# LOVE_LED_CARD_2021-05-20.net
KiCad netlist of a schematic drawn in EasyEDA
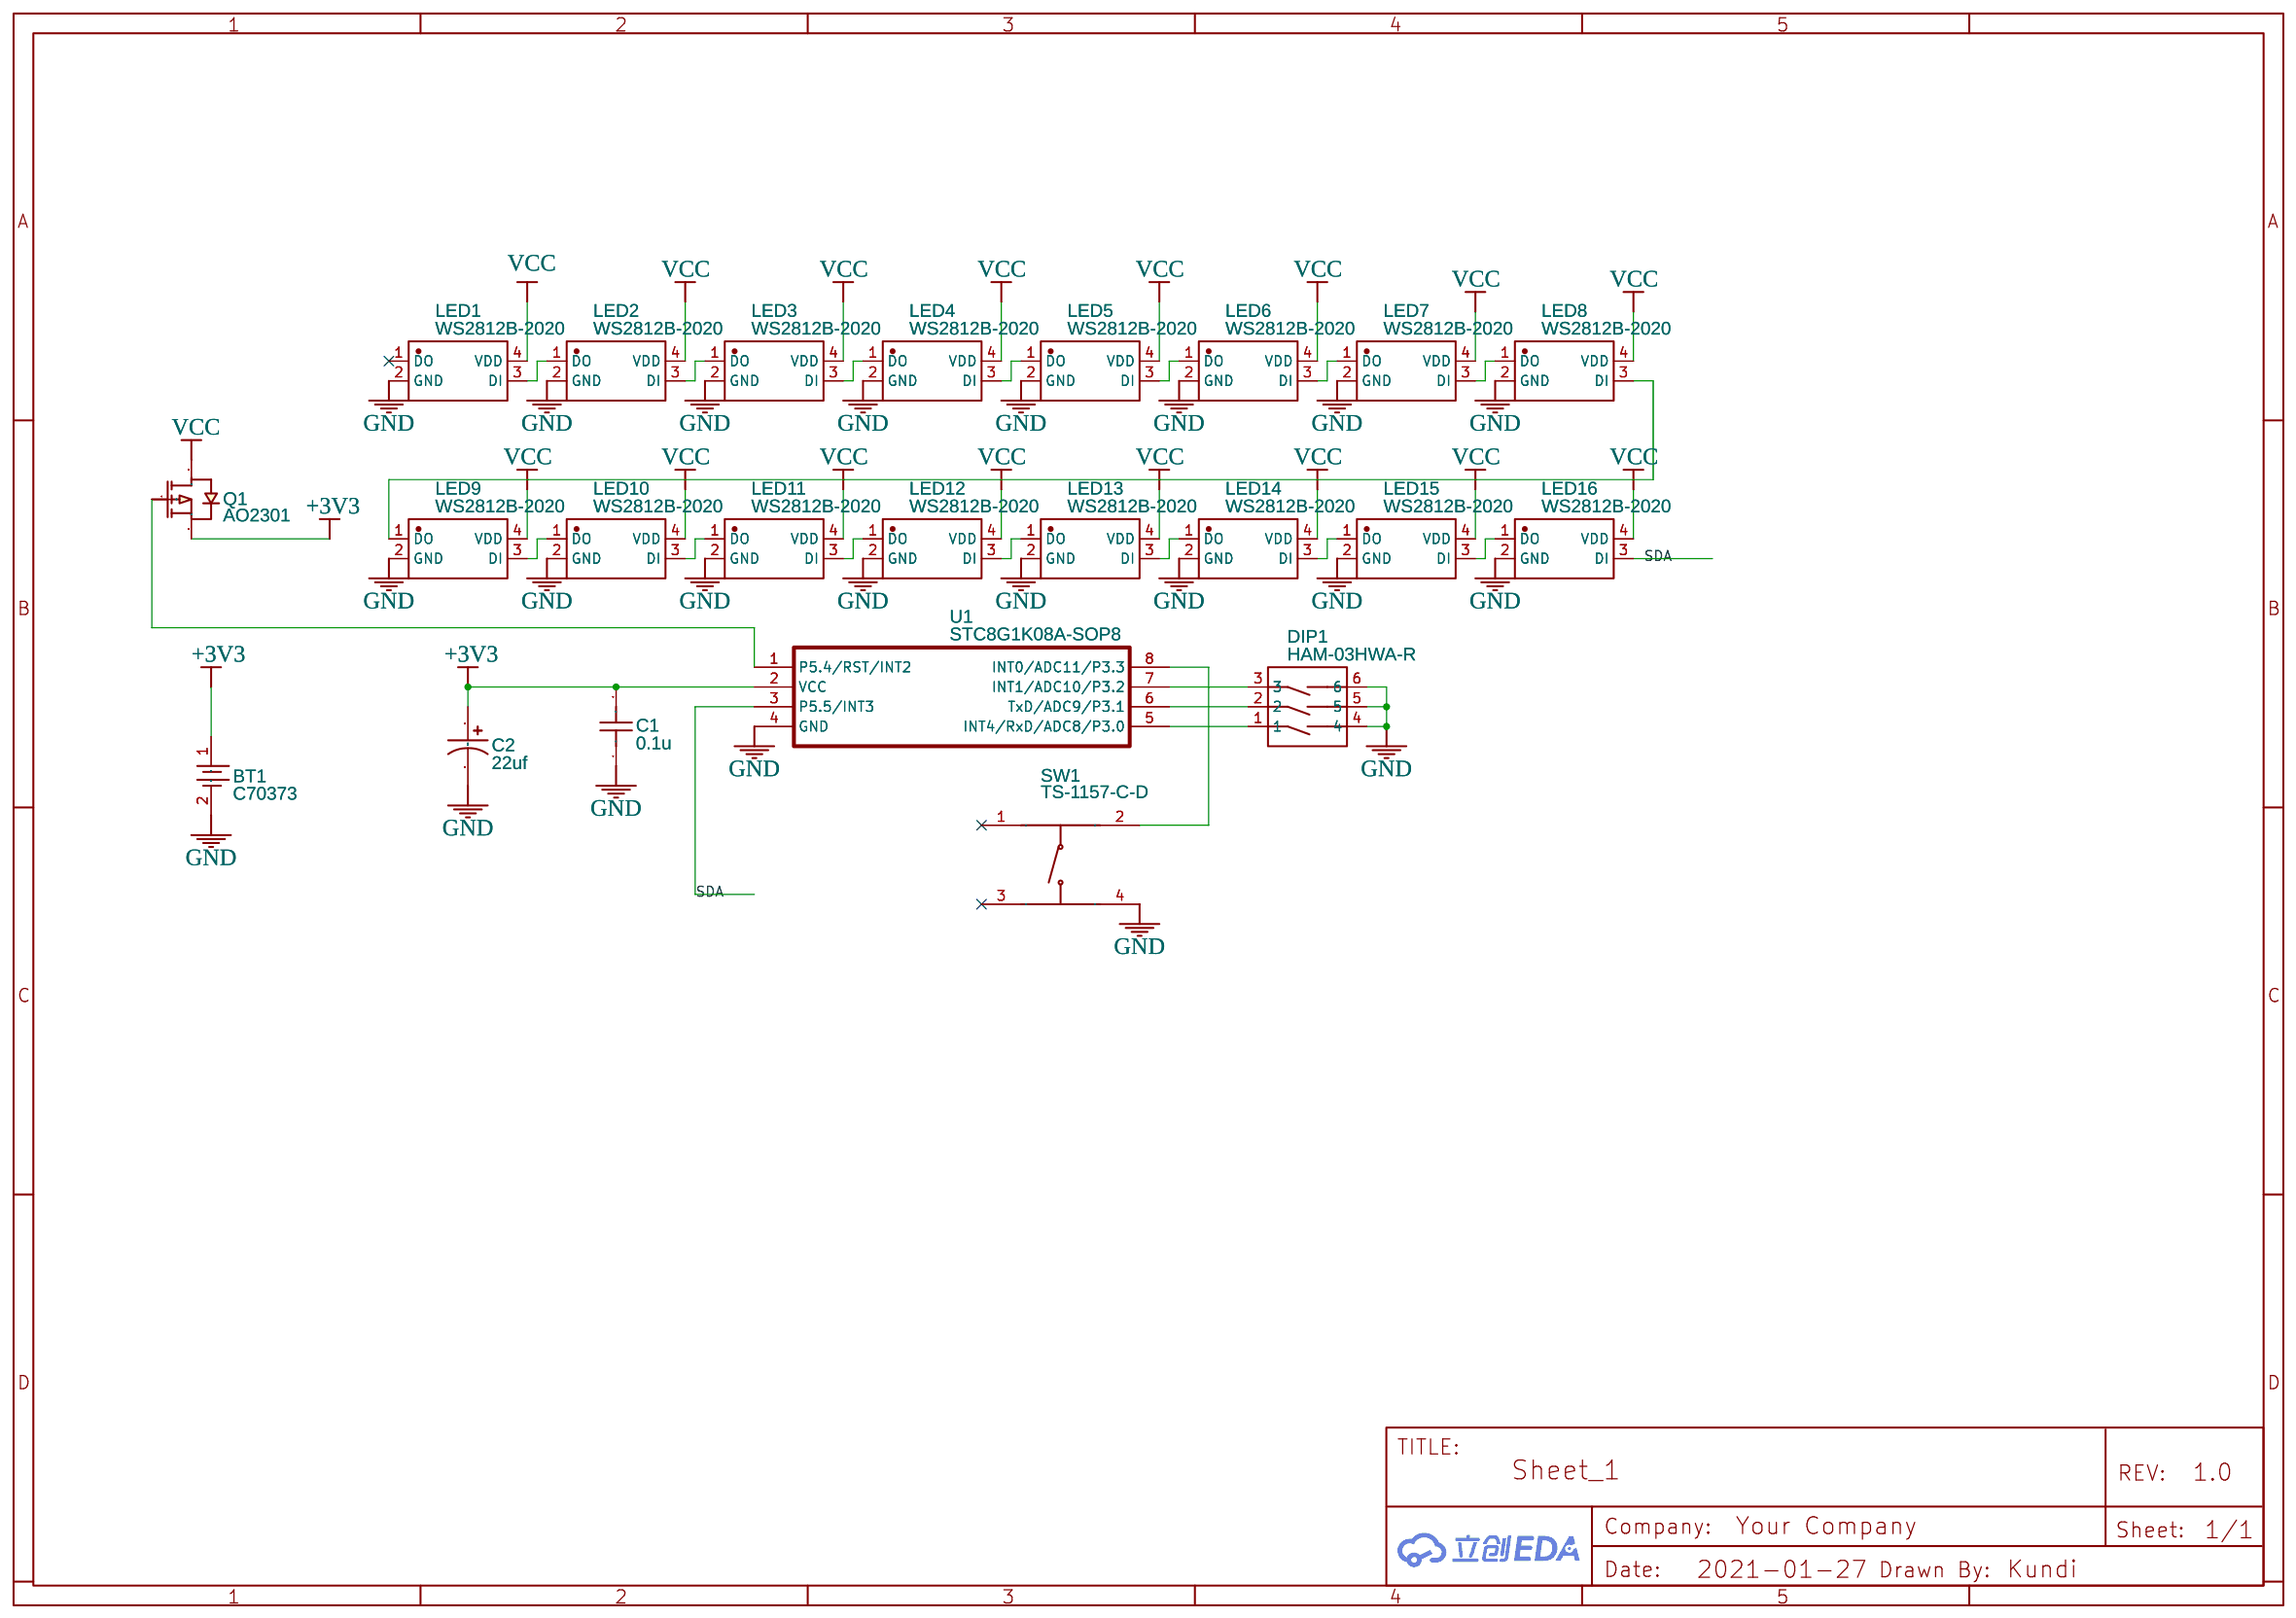
[diagram p0: schematic sheet]

(export (version "E")
  (design (tool "Eeschema 10.0.6"))
  (components
    (comp (ref "BT1") (value "C70373") (libsource (lib "") (part "C70373")))
    (comp (ref "C1") (value "0.1u") (libsource (lib "") (part "C_0805_US")))
    (comp (ref "C2") (value "22uf") (libsource (lib "") (part "C_Tan_SMD_A_US")))
    (comp (ref "DIP1")
      (value "HAM-03HWA-R")
      (fields (field (name "BOM_Supplier Part") "C4666"))
      (libsource (lib "") (part "HAM-03HWA-R"))
    )
    (comp (ref "LED1")
      (value "WS2812B-2020")
      (fields (field (name "BOM_Supplier Part") "C965555"))
      (libsource (lib "") (part "WS2812B-2020"))
    )
    (comp (ref "LED2")
      (value "WS2812B-2020")
      (fields (field (name "BOM_Supplier Part") "C965555"))
      (libsource (lib "") (part "WS2812B-2020"))
    )
    (comp (ref "LED3")
      (value "WS2812B-2020")
      (fields (field (name "BOM_Supplier Part") "C965555"))
      (libsource (lib "") (part "WS2812B-2020"))
    )
    (comp (ref "LED4")
      (value "WS2812B-2020")
      (fields (field (name "BOM_Supplier Part") "C965555"))
      (libsource (lib "") (part "WS2812B-2020"))
    )
    (comp (ref "LED5")
      (value "WS2812B-2020")
      (fields (field (name "BOM_Supplier Part") "C965555"))
      (libsource (lib "") (part "WS2812B-2020"))
    )
    (comp (ref "LED6")
      (value "WS2812B-2020")
      (fields (field (name "BOM_Supplier Part") "C965555"))
      (libsource (lib "") (part "WS2812B-2020"))
    )
    (comp (ref "LED7")
      (value "WS2812B-2020")
      (fields (field (name "BOM_Supplier Part") "C965555"))
      (libsource (lib "") (part "WS2812B-2020"))
    )
    (comp (ref "LED8")
      (value "WS2812B-2020")
      (fields (field (name "BOM_Supplier Part") "C965555"))
      (libsource (lib "") (part "WS2812B-2020"))
    )
    (comp (ref "LED9")
      (value "WS2812B-2020")
      (fields (field (name "BOM_Supplier Part") "C965555"))
      (libsource (lib "") (part "WS2812B-2020"))
    )
    (comp (ref "LED10")
      (value "WS2812B-2020")
      (fields (field (name "BOM_Supplier Part") "C965555"))
      (libsource (lib "") (part "WS2812B-2020"))
    )
    (comp (ref "LED11")
      (value "WS2812B-2020")
      (fields (field (name "BOM_Supplier Part") "C965555"))
      (libsource (lib "") (part "WS2812B-2020"))
    )
    (comp (ref "LED12")
      (value "WS2812B-2020")
      (fields (field (name "BOM_Supplier Part") "C965555"))
      (libsource (lib "") (part "WS2812B-2020"))
    )
    (comp (ref "LED13")
      (value "WS2812B-2020")
      (fields (field (name "BOM_Supplier Part") "C965555"))
      (libsource (lib "") (part "WS2812B-2020"))
    )
    (comp (ref "LED14")
      (value "WS2812B-2020")
      (fields (field (name "BOM_Supplier Part") "C965555"))
      (libsource (lib "") (part "WS2812B-2020"))
    )
    (comp (ref "LED15")
      (value "WS2812B-2020")
      (fields (field (name "BOM_Supplier Part") "C965555"))
      (libsource (lib "") (part "WS2812B-2020"))
    )
    (comp (ref "LED16")
      (value "WS2812B-2020")
      (fields (field (name "BOM_Supplier Part") "C965555"))
      (libsource (lib "") (part "WS2812B-2020"))
    )
    (comp (ref "Q1")
      (value "AO2301")
      (fields (field (name "BOM_Supplier Part") "C693104"))
      (libsource (lib "") (part "AO2301"))
    )
    (comp (ref "SW1")
      (value "TS-1157-C-D")
      (fields (field (name "BOM_Supplier Part") "C609868"))
      (libsource (lib "") (part "TS-1157-C-D"))
    )
    (comp (ref "U1") (value "STC8G1K08A-SOP8") (libsource (lib "") (part "STC8G1K08A-SOP8")))
  )
  (nets
    (net (code "1") (name "+3V3") (class "Default")
      (node (ref "BT1") (pin "1") (pinfunction "1_1") (pintype "input"))
      (node (ref "C1") (pin "2") (pinfunction "2_2") (pintype "unspecified"))
      (node (ref "C2") (pin "1") (pinfunction "1_1") (pintype "unspecified"))
      (node (ref "Q1") (pin "2") (pinfunction "S_2") (pintype "unspecified"))
      (node (ref "U1") (pin "2") (pinfunction "VCC_2") (pintype "unspecified"))
    )
    (net (code "2") (name "/SDA") (class "Default")
      (node (ref "LED16") (pin "3") (pinfunction "DI_3") (pintype "unspecified"))
      (node (ref "U1") (pin "3") (pinfunction "P5.5/INT3_3") (pintype "unspecified"))
    )
    (net (code "3") (name "GND") (class "Default")
      (node (ref "BT1") (pin "2") (pinfunction "2_2") (pintype "input"))
      (node (ref "C1") (pin "1") (pinfunction "1_1") (pintype "unspecified"))
      (node (ref "C2") (pin "2") (pinfunction "2_2") (pintype "unspecified"))
      (node (ref "DIP1") (pin "4") (pinfunction "4_4") (pintype "unspecified"))
      (node (ref "DIP1") (pin "5") (pinfunction "5_5") (pintype "unspecified"))
      (node (ref "DIP1") (pin "6") (pinfunction "6_6") (pintype "unspecified"))
      (node (ref "LED1") (pin "2") (pinfunction "GND_2") (pintype "unspecified"))
      (node (ref "LED10") (pin "2") (pinfunction "GND_2") (pintype "unspecified"))
      (node (ref "LED11") (pin "2") (pinfunction "GND_2") (pintype "unspecified"))
      (node (ref "LED12") (pin "2") (pinfunction "GND_2") (pintype "unspecified"))
      (node (ref "LED13") (pin "2") (pinfunction "GND_2") (pintype "unspecified"))
      (node (ref "LED14") (pin "2") (pinfunction "GND_2") (pintype "unspecified"))
      (node (ref "LED15") (pin "2") (pinfunction "GND_2") (pintype "unspecified"))
      (node (ref "LED16") (pin "2") (pinfunction "GND_2") (pintype "unspecified"))
      (node (ref "LED2") (pin "2") (pinfunction "GND_2") (pintype "unspecified"))
      (node (ref "LED3") (pin "2") (pinfunction "GND_2") (pintype "unspecified"))
      (node (ref "LED4") (pin "2") (pinfunction "GND_2") (pintype "unspecified"))
      (node (ref "LED5") (pin "2") (pinfunction "GND_2") (pintype "unspecified"))
      (node (ref "LED6") (pin "2") (pinfunction "GND_2") (pintype "unspecified"))
      (node (ref "LED7") (pin "2") (pinfunction "GND_2") (pintype "unspecified"))
      (node (ref "LED8") (pin "2") (pinfunction "GND_2") (pintype "unspecified"))
      (node (ref "LED9") (pin "2") (pinfunction "GND_2") (pintype "unspecified"))
      (node (ref "SW1") (pin "4") (pinfunction "D_4") (pintype "unspecified"))
      (node (ref "U1") (pin "4") (pinfunction "GND_4") (pintype "unspecified"))
    )
    (net (code "4") (name "Net-(LED1-DI)") (class "Default")
      (node (ref "LED1") (pin "3") (pinfunction "DI_3") (pintype "unspecified"))
      (node (ref "LED2") (pin "1") (pinfunction "DO_1") (pintype "unspecified"))
    )
    (net (code "5") (name "Net-(LED2-DI)") (class "Default")
      (node (ref "LED2") (pin "3") (pinfunction "DI_3") (pintype "unspecified"))
      (node (ref "LED3") (pin "1") (pinfunction "DO_1") (pintype "unspecified"))
    )
    (net (code "6") (name "Net-(LED3-DI)") (class "Default")
      (node (ref "LED3") (pin "3") (pinfunction "DI_3") (pintype "unspecified"))
      (node (ref "LED4") (pin "1") (pinfunction "DO_1") (pintype "unspecified"))
    )
    (net (code "7") (name "Net-(LED4-DI)") (class "Default")
      (node (ref "LED4") (pin "3") (pinfunction "DI_3") (pintype "unspecified"))
      (node (ref "LED5") (pin "1") (pinfunction "DO_1") (pintype "unspecified"))
    )
    (net (code "8") (name "Net-(LED5-DI)") (class "Default")
      (node (ref "LED5") (pin "3") (pinfunction "DI_3") (pintype "unspecified"))
      (node (ref "LED6") (pin "1") (pinfunction "DO_1") (pintype "unspecified"))
    )
    (net (code "9") (name "Net-(LED6-DI)") (class "Default")
      (node (ref "LED6") (pin "3") (pinfunction "DI_3") (pintype "unspecified"))
      (node (ref "LED7") (pin "1") (pinfunction "DO_1") (pintype "unspecified"))
    )
    (net (code "10") (name "Net-(LED7-DI)") (class "Default")
      (node (ref "LED7") (pin "3") (pinfunction "DI_3") (pintype "unspecified"))
      (node (ref "LED8") (pin "1") (pinfunction "DO_1") (pintype "unspecified"))
    )
    (net (code "11") (name "Net-(LED8-DI)") (class "Default")
      (node (ref "LED8") (pin "3") (pinfunction "DI_3") (pintype "unspecified"))
      (node (ref "LED9") (pin "1") (pinfunction "DO_1") (pintype "unspecified"))
    )
    (net (code "12") (name "Net-(LED10-DI)") (class "Default")
      (node (ref "LED10") (pin "3") (pinfunction "DI_3") (pintype "unspecified"))
      (node (ref "LED11") (pin "1") (pinfunction "DO_1") (pintype "unspecified"))
    )
    (net (code "13") (name "Net-(LED10-DO)") (class "Default")
      (node (ref "LED10") (pin "1") (pinfunction "DO_1") (pintype "unspecified"))
      (node (ref "LED9") (pin "3") (pinfunction "DI_3") (pintype "unspecified"))
    )
    (net (code "14") (name "Net-(LED11-DI)") (class "Default")
      (node (ref "LED11") (pin "3") (pinfunction "DI_3") (pintype "unspecified"))
      (node (ref "LED12") (pin "1") (pinfunction "DO_1") (pintype "unspecified"))
    )
    (net (code "15") (name "Net-(LED12-DI)") (class "Default")
      (node (ref "LED12") (pin "3") (pinfunction "DI_3") (pintype "unspecified"))
      (node (ref "LED13") (pin "1") (pinfunction "DO_1") (pintype "unspecified"))
    )
    (net (code "16") (name "Net-(LED13-DI)") (class "Default")
      (node (ref "LED13") (pin "3") (pinfunction "DI_3") (pintype "unspecified"))
      (node (ref "LED14") (pin "1") (pinfunction "DO_1") (pintype "unspecified"))
    )
    (net (code "17") (name "Net-(LED14-DI)") (class "Default")
      (node (ref "LED14") (pin "3") (pinfunction "DI_3") (pintype "unspecified"))
      (node (ref "LED15") (pin "1") (pinfunction "DO_1") (pintype "unspecified"))
    )
    (net (code "18") (name "Net-(LED15-DI)") (class "Default")
      (node (ref "LED15") (pin "3") (pinfunction "DI_3") (pintype "unspecified"))
      (node (ref "LED16") (pin "1") (pinfunction "DO_1") (pintype "unspecified"))
    )
    (net (code "19") (name "Net-(Q1-G)") (class "Default")
      (node (ref "Q1") (pin "1") (pinfunction "G_1") (pintype "unspecified"))
      (node (ref "U1") (pin "1") (pinfunction "P5.4/RST/INT2_1") (pintype "unspecified"))
    )
    (net (code "20") (name "Net-(SW1-B)") (class "Default")
      (node (ref "SW1") (pin "2") (pinfunction "B_2") (pintype "unspecified"))
      (node (ref "U1") (pin "8") (pinfunction "INT0/ADC11/P3.3_8") (pintype "unspecified"))
    )
    (net (code "21") (name "Net-(U1-INT1{slash}ADC10{slash}P3.2)") (class "Default")
      (node (ref "DIP1") (pin "3") (pinfunction "3_3") (pintype "unspecified"))
      (node (ref "U1") (pin "7") (pinfunction "INT1/ADC10/P3.2_7") (pintype "unspecified"))
    )
    (net (code "22") (name "Net-(U1-INT4{slash}RxD{slash}ADC8{slash}P3.0)") (class "Default")
      (node (ref "DIP1") (pin "1") (pinfunction "1_1") (pintype "unspecified"))
      (node (ref "U1") (pin "5") (pinfunction "INT4/RxD/ADC8/P3.0_5") (pintype "unspecified"))
    )
    (net (code "23") (name "Net-(U1-TxD{slash}ADC9{slash}P3.1)") (class "Default")
      (node (ref "DIP1") (pin "2") (pinfunction "2_2") (pintype "unspecified"))
      (node (ref "U1") (pin "6") (pinfunction "TxD/ADC9/P3.1_6") (pintype "unspecified"))
    )
    (net (code "24") (name "VCC") (class "Default")
      (node (ref "LED1") (pin "4") (pinfunction "VDD_4") (pintype "unspecified"))
      (node (ref "LED10") (pin "4") (pinfunction "VDD_4") (pintype "unspecified"))
      (node (ref "LED11") (pin "4") (pinfunction "VDD_4") (pintype "unspecified"))
      (node (ref "LED12") (pin "4") (pinfunction "VDD_4") (pintype "unspecified"))
      (node (ref "LED13") (pin "4") (pinfunction "VDD_4") (pintype "unspecified"))
      (node (ref "LED14") (pin "4") (pinfunction "VDD_4") (pintype "unspecified"))
      (node (ref "LED15") (pin "4") (pinfunction "VDD_4") (pintype "unspecified"))
      (node (ref "LED16") (pin "4") (pinfunction "VDD_4") (pintype "unspecified"))
      (node (ref "LED2") (pin "4") (pinfunction "VDD_4") (pintype "unspecified"))
      (node (ref "LED3") (pin "4") (pinfunction "VDD_4") (pintype "unspecified"))
      (node (ref "LED4") (pin "4") (pinfunction "VDD_4") (pintype "unspecified"))
      (node (ref "LED5") (pin "4") (pinfunction "VDD_4") (pintype "unspecified"))
      (node (ref "LED6") (pin "4") (pinfunction "VDD_4") (pintype "unspecified"))
      (node (ref "LED7") (pin "4") (pinfunction "VDD_4") (pintype "unspecified"))
      (node (ref "LED8") (pin "4") (pinfunction "VDD_4") (pintype "unspecified"))
      (node (ref "LED9") (pin "4") (pinfunction "VDD_4") (pintype "unspecified"))
      (node (ref "Q1") (pin "3") (pinfunction "D_3") (pintype "unspecified"))
    )
    (net (code "25") (name "unconnected-(LED1-DO-Pad1)") (class "Default")
      (node (ref "LED1") (pin "1") (pinfunction "DO_1") (pintype "unspecified+no_connect"))
    )
    (net (code "26") (name "unconnected-(SW1-A-Pad1)") (class "Default")
      (node (ref "SW1") (pin "1") (pinfunction "A_1") (pintype "unspecified+no_connect"))
    )
    (net (code "27") (name "unconnected-(SW1-C-Pad3)") (class "Default")
      (node (ref "SW1") (pin "3") (pinfunction "C_3") (pintype "unspecified+no_connect"))
    )
  )
)
